# Amplifier_Module_C.net
KiCad netlist of a schematic drawn in EasyEDA Pro
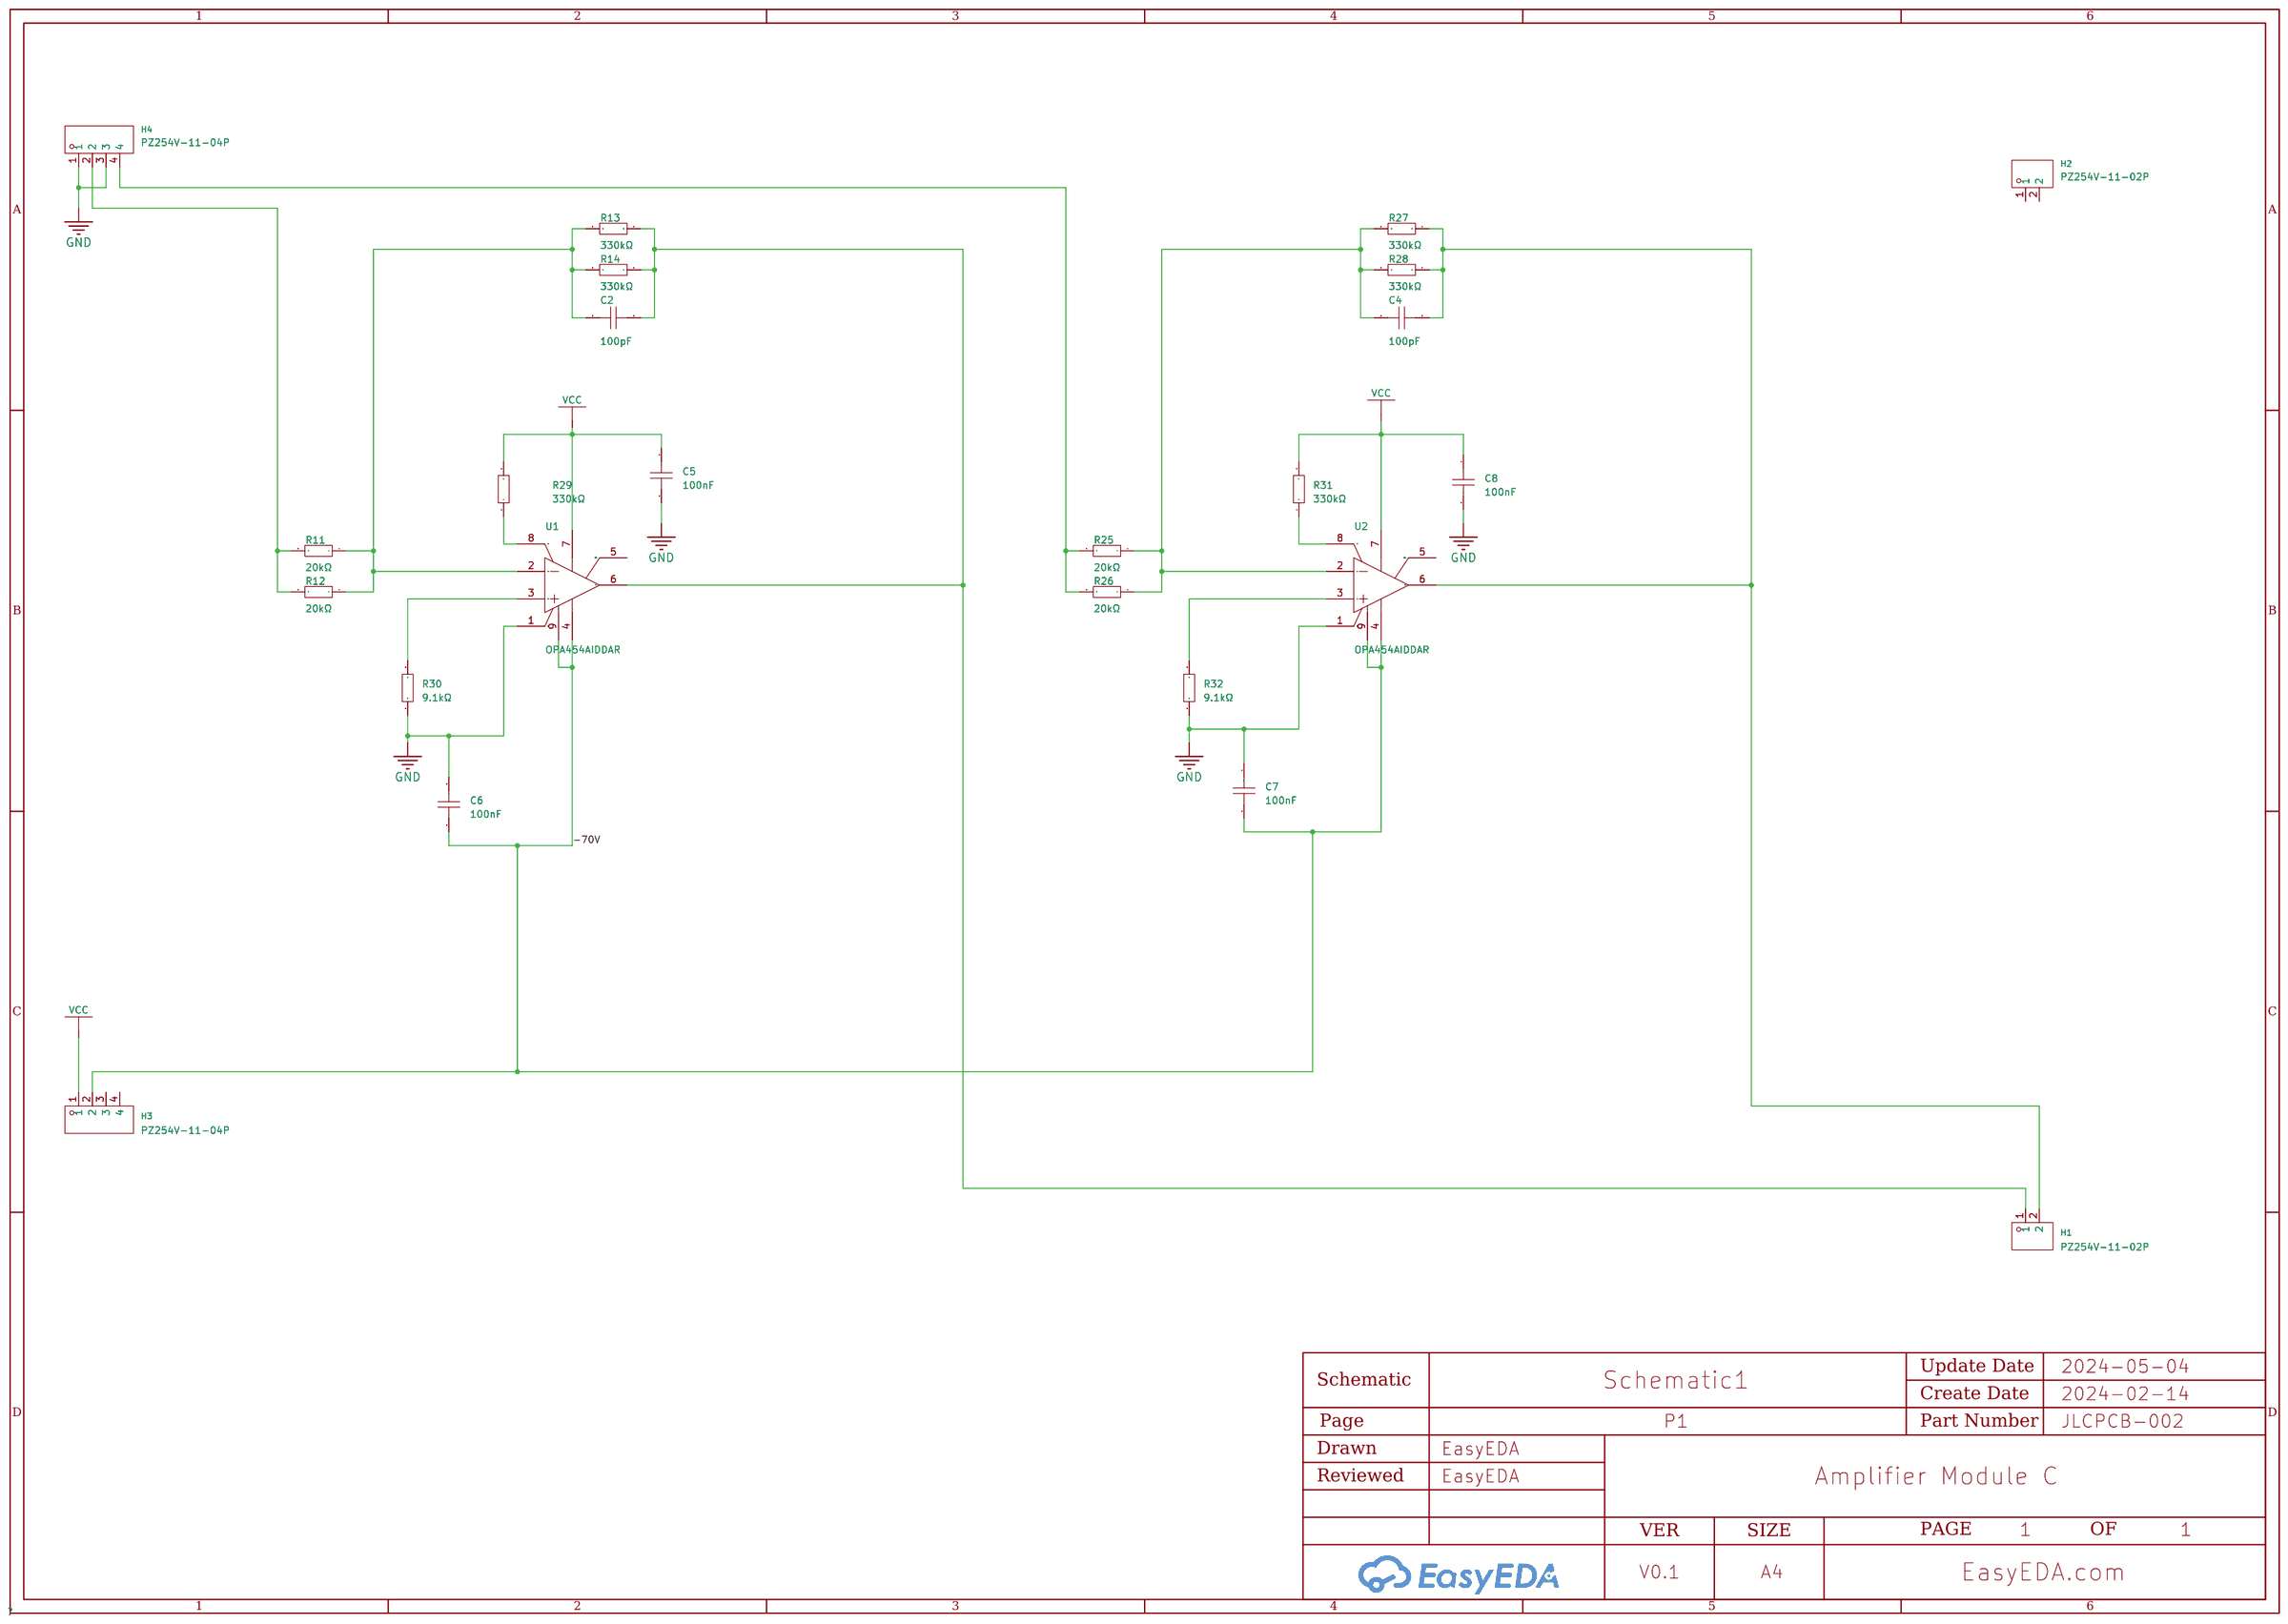
[diagram p0: schematic sheet]

(export (version "E")
  (design (tool "Eeschema 10.0.6"))
  (components
    (comp (ref "C2")
      (value "100pF")
      (footprint "easyedapro:C0603")
      (fields (field (name "Manufacturer Part") "0603CG101J101NT") (field (name "Manufacturer") "FH(风华)"))
      (libsource (lib "easyedapro") (part "CAP"))
    )
    (comp (ref "C4")
      (value "100pF")
      (footprint "easyedapro:C0603")
      (fields (field (name "Manufacturer Part") "0603CG101J101NT") (field (name "Manufacturer") "FH(风华)"))
      (libsource (lib "easyedapro") (part "CAP"))
    )
    (comp (ref "C5")
      (value "100nF")
      (footprint "easyedapro:C0603")
      (fields (field (name "Manufacturer Part") "0603B104K101NT") (field (name "Manufacturer") "FH(风华)"))
      (libsource (lib "easyedapro") (part "CAP"))
    )
    (comp (ref "C6")
      (value "100nF")
      (footprint "easyedapro:C0603")
      (fields (field (name "Manufacturer Part") "0603B104K101NT") (field (name "Manufacturer") "FH(风华)"))
      (libsource (lib "easyedapro") (part "CAP"))
    )
    (comp (ref "C7")
      (value "100nF")
      (footprint "easyedapro:C0603")
      (fields (field (name "Manufacturer Part") "0603B104K101NT") (field (name "Manufacturer") "FH(风华)"))
      (libsource (lib "easyedapro") (part "CAP"))
    )
    (comp (ref "C8")
      (value "100nF")
      (footprint "easyedapro:C0603")
      (fields (field (name "Manufacturer Part") "0603B104K101NT") (field (name "Manufacturer") "FH(风华)"))
      (libsource (lib "easyedapro") (part "CAP"))
    )
    (comp (ref "H1")
      (value "PZ254V-11-02P")
      (footprint "easyedapro:HDR-TH_2P-P2.54-V-M")
      (fields (field (name "Manufacturer") "XFCN(兴飞)"))
      (libsource (lib "easyedapro") (part "PZ254V-11-02P"))
    )
    (comp (ref "H2")
      (value "PZ254V-11-02P")
      (footprint "easyedapro:HDR-TH_2P-P2.54-V-M")
      (fields (field (name "Manufacturer") "XFCN(兴飞)"))
      (libsource (lib "easyedapro") (part "PZ254V-11-02P"))
    )
    (comp (ref "H3")
      (value "PZ254V-11-04P")
      (footprint "easyedapro:HDR-TH_4P-P2.54-V-M")
      (fields (field (name "Manufacturer") "XFCN(兴飞)"))
      (libsource (lib "easyedapro") (part "PZ254V-11-04P_C2691448"))
    )
    (comp (ref "H4")
      (value "PZ254V-11-04P")
      (footprint "easyedapro:HDR-TH_4P-P2.54-V-M")
      (fields (field (name "Manufacturer") "XFCN(兴飞)"))
      (libsource (lib "easyedapro") (part "PZ254V-11-04P_C2691448"))
    )
    (comp (ref "R11")
      (value "20kΩ")
      (footprint "easyedapro:R0603")
      (fields
        (field (name "Manufacturer Part") "0603WAF2002T5E")
        (field (name "Manufacturer") "UNI-ROYAL(厚声)")
      )
      (libsource (lib "easyedapro") (part "Res"))
    )
    (comp (ref "R12")
      (value "20kΩ")
      (footprint "easyedapro:R0603")
      (fields
        (field (name "Manufacturer Part") "0603WAF2002T5E")
        (field (name "Manufacturer") "UNI-ROYAL(厚声)")
      )
      (libsource (lib "easyedapro") (part "Res"))
    )
    (comp (ref "R13")
      (value "330kΩ")
      (footprint "easyedapro:R0603")
      (fields
        (field (name "Manufacturer Part") "0603WAF3303T5E")
        (field (name "Manufacturer") "UNI-ROYAL(厚声)")
      )
      (libsource (lib "easyedapro") (part "Res"))
    )
    (comp (ref "R14")
      (value "330kΩ")
      (footprint "easyedapro:R0603")
      (fields
        (field (name "Manufacturer Part") "0603WAF3303T5E")
        (field (name "Manufacturer") "UNI-ROYAL(厚声)")
      )
      (libsource (lib "easyedapro") (part "Res"))
    )
    (comp (ref "R25")
      (value "20kΩ")
      (footprint "easyedapro:R0603")
      (fields
        (field (name "Manufacturer Part") "0603WAF2002T5E")
        (field (name "Manufacturer") "UNI-ROYAL(厚声)")
      )
      (libsource (lib "easyedapro") (part "Res"))
    )
    (comp (ref "R26")
      (value "20kΩ")
      (footprint "easyedapro:R0603")
      (fields
        (field (name "Manufacturer Part") "0603WAF2002T5E")
        (field (name "Manufacturer") "UNI-ROYAL(厚声)")
      )
      (libsource (lib "easyedapro") (part "Res"))
    )
    (comp (ref "R27")
      (value "330kΩ")
      (footprint "easyedapro:R0603")
      (fields
        (field (name "Manufacturer Part") "0603WAF3303T5E")
        (field (name "Manufacturer") "UNI-ROYAL(厚声)")
      )
      (libsource (lib "easyedapro") (part "Res"))
    )
    (comp (ref "R28")
      (value "330kΩ")
      (footprint "easyedapro:R0603")
      (fields
        (field (name "Manufacturer Part") "0603WAF3303T5E")
        (field (name "Manufacturer") "UNI-ROYAL(厚声)")
      )
      (libsource (lib "easyedapro") (part "Res"))
    )
    (comp (ref "R29")
      (value "330kΩ")
      (footprint "easyedapro:R0603")
      (fields
        (field (name "Manufacturer Part") "0603WAF3303T5E")
        (field (name "Manufacturer") "UNI-ROYAL(厚声)")
      )
      (libsource (lib "easyedapro") (part "Res"))
    )
    (comp (ref "R30")
      (value "9.1kΩ")
      (footprint "easyedapro:R0603")
      (fields
        (field (name "Manufacturer Part") "0603WAF9101T5E")
        (field (name "Manufacturer") "UNI-ROYAL(厚声)")
      )
      (libsource (lib "easyedapro") (part "Res"))
    )
    (comp (ref "R31")
      (value "330kΩ")
      (footprint "easyedapro:R0603")
      (fields
        (field (name "Manufacturer Part") "0603WAF3303T5E")
        (field (name "Manufacturer") "UNI-ROYAL(厚声)")
      )
      (libsource (lib "easyedapro") (part "Res"))
    )
    (comp (ref "R32")
      (value "9.1kΩ")
      (footprint "easyedapro:R0603")
      (fields
        (field (name "Manufacturer Part") "0603WAF9101T5E")
        (field (name "Manufacturer") "UNI-ROYAL(厚声)")
      )
      (libsource (lib "easyedapro") (part "Res"))
    )
    (comp (ref "U1")
      (value "OPA454AIDDAR")
      (footprint "easyedapro:SOIC-8_L4.9-W3.9-P1.27-LS6.0-BL-EP")
      (fields (field (name "Manufacturer") "TI(德州仪器)"))
      (libsource (lib "easyedapro") (part "OPA454AIDDAR"))
    )
    (comp (ref "U2")
      (value "OPA454AIDDAR")
      (footprint "easyedapro:SOIC-8_L4.9-W3.9-P1.27-LS6.0-BL-EP")
      (fields (field (name "Manufacturer") "TI(德州仪器)"))
      (libsource (lib "easyedapro") (part "OPA454AIDDAR"))
    )
  )
  (nets
    (net (code "1") (name "/-70V") (class "Default")
      (node (ref "C6") (pin "2") (pinfunction "2_2") (pintype "input"))
      (node (ref "C7") (pin "2") (pinfunction "2_2") (pintype "input"))
      (node (ref "H3") (pin "2") (pinfunction "2_2") (pintype "input"))
      (node (ref "U1") (pin "4") (pinfunction "V-_4") (pintype "unspecified"))
      (node (ref "U1") (pin "9") (pinfunction "EP_9") (pintype "unspecified"))
      (node (ref "U2") (pin "4") (pinfunction "V-_4") (pintype "unspecified"))
      (node (ref "U2") (pin "9") (pinfunction "EP_9") (pintype "unspecified"))
    )
    (net (code "2") (name "GND") (class "Default")
      (node (ref "C5") (pin "2") (pinfunction "2_2") (pintype "input"))
      (node (ref "C6") (pin "1") (pinfunction "1_1") (pintype "input"))
      (node (ref "C7") (pin "1") (pinfunction "1_1") (pintype "input"))
      (node (ref "C8") (pin "2") (pinfunction "2_2") (pintype "input"))
      (node (ref "H4") (pin "1") (pinfunction "1_1") (pintype "input"))
      (node (ref "H4") (pin "3") (pinfunction "3_3") (pintype "input"))
      (node (ref "R30") (pin "1") (pinfunction "1_1") (pintype "input"))
      (node (ref "R32") (pin "1") (pinfunction "1_1") (pintype "input"))
      (node (ref "U1") (pin "1") (pinfunction "ED_COM_1") (pintype "unspecified"))
      (node (ref "U2") (pin "1") (pinfunction "ED_COM_1") (pintype "unspecified"))
    )
    (net (code "3") (name "Net-(H4-Pad2)") (class "Default")
      (node (ref "H4") (pin "2") (pinfunction "2_2") (pintype "input"))
      (node (ref "R11") (pin "2") (pinfunction "2_2") (pintype "input"))
      (node (ref "R12") (pin "2") (pinfunction "2_2") (pintype "input"))
    )
    (net (code "4") (name "Net-(H4-Pad4)") (class "Default")
      (node (ref "H4") (pin "4") (pinfunction "4_4") (pintype "input"))
      (node (ref "R25") (pin "2") (pinfunction "2_2") (pintype "input"))
      (node (ref "R26") (pin "2") (pinfunction "2_2") (pintype "input"))
    )
    (net (code "5") (name "Net-(U1-ED)") (class "Default")
      (node (ref "R29") (pin "1") (pinfunction "1_1") (pintype "input"))
      (node (ref "U1") (pin "8") (pinfunction "ED_8") (pintype "unspecified"))
    )
    (net (code "6") (name "Net-(U1-IN+)") (class "Default")
      (node (ref "R30") (pin "2") (pinfunction "2_2") (pintype "input"))
      (node (ref "U1") (pin "3") (pinfunction "IN+_3") (pintype "unspecified"))
    )
    (net (code "7") (name "Net-(U1-IN-)") (class "Default")
      (node (ref "C2") (pin "2") (pinfunction "2_2") (pintype "input"))
      (node (ref "R11") (pin "1") (pinfunction "1_1") (pintype "input"))
      (node (ref "R12") (pin "1") (pinfunction "1_1") (pintype "input"))
      (node (ref "R13") (pin "2") (pinfunction "2_2") (pintype "input"))
      (node (ref "R14") (pin "2") (pinfunction "2_2") (pintype "input"))
      (node (ref "U1") (pin "2") (pinfunction "IN-_2") (pintype "unspecified"))
    )
    (net (code "8") (name "Net-(U1-OUT)") (class "Default")
      (node (ref "C2") (pin "1") (pinfunction "1_1") (pintype "input"))
      (node (ref "H1") (pin "1") (pinfunction "1_1") (pintype "input"))
      (node (ref "R13") (pin "1") (pinfunction "1_1") (pintype "input"))
      (node (ref "R14") (pin "1") (pinfunction "1_1") (pintype "input"))
      (node (ref "U1") (pin "6") (pinfunction "OUT_6") (pintype "output"))
    )
    (net (code "9") (name "Net-(U2-ED)") (class "Default")
      (node (ref "R31") (pin "1") (pinfunction "1_1") (pintype "input"))
      (node (ref "U2") (pin "8") (pinfunction "ED_8") (pintype "unspecified"))
    )
    (net (code "10") (name "Net-(U2-IN+)") (class "Default")
      (node (ref "R32") (pin "2") (pinfunction "2_2") (pintype "input"))
      (node (ref "U2") (pin "3") (pinfunction "IN+_3") (pintype "unspecified"))
    )
    (net (code "11") (name "Net-(U2-IN-)") (class "Default")
      (node (ref "C4") (pin "2") (pinfunction "2_2") (pintype "input"))
      (node (ref "R25") (pin "1") (pinfunction "1_1") (pintype "input"))
      (node (ref "R26") (pin "1") (pinfunction "1_1") (pintype "input"))
      (node (ref "R27") (pin "2") (pinfunction "2_2") (pintype "input"))
      (node (ref "R28") (pin "2") (pinfunction "2_2") (pintype "input"))
      (node (ref "U2") (pin "2") (pinfunction "IN-_2") (pintype "unspecified"))
    )
    (net (code "12") (name "Net-(U2-OUT)") (class "Default")
      (node (ref "C4") (pin "1") (pinfunction "1_1") (pintype "input"))
      (node (ref "H1") (pin "2") (pinfunction "2_2") (pintype "input"))
      (node (ref "R27") (pin "1") (pinfunction "1_1") (pintype "input"))
      (node (ref "R28") (pin "1") (pinfunction "1_1") (pintype "input"))
      (node (ref "U2") (pin "6") (pinfunction "OUT_6") (pintype "output"))
    )
    (net (code "13") (name "VCC") (class "Default")
      (node (ref "C5") (pin "1") (pinfunction "1_1") (pintype "input"))
      (node (ref "C8") (pin "1") (pinfunction "1_1") (pintype "input"))
      (node (ref "H3") (pin "1") (pinfunction "1_1") (pintype "input"))
      (node (ref "R29") (pin "2") (pinfunction "2_2") (pintype "input"))
      (node (ref "R31") (pin "2") (pinfunction "2_2") (pintype "input"))
      (node (ref "U1") (pin "7") (pinfunction "V+_7") (pintype "unspecified"))
      (node (ref "U2") (pin "7") (pinfunction "V+_7") (pintype "unspecified"))
    )
    (net (code "14") (name "unconnected-(H2-Pad1)") (class "Default")
      (node (ref "H2") (pin "1") (pinfunction "1_1") (pintype "input"))
    )
    (net (code "15") (name "unconnected-(H2-Pad2)") (class "Default")
      (node (ref "H2") (pin "2") (pinfunction "2_2") (pintype "input"))
    )
    (net (code "16") (name "unconnected-(H3-Pad3)") (class "Default")
      (node (ref "H3") (pin "3") (pinfunction "3_3") (pintype "input"))
    )
    (net (code "17") (name "unconnected-(H3-Pad4)") (class "Default")
      (node (ref "H3") (pin "4") (pinfunction "4_4") (pintype "input"))
    )
    (net (code "18") (name "unconnected-(U1-STATUS_FLAG-Pad5)") (class "Default")
      (node (ref "U1") (pin "5") (pinfunction "STATUS_FLAG_5") (pintype "unspecified"))
    )
    (net (code "19") (name "unconnected-(U2-STATUS_FLAG-Pad5)") (class "Default")
      (node (ref "U2") (pin "5") (pinfunction "STATUS_FLAG_5") (pintype "unspecified"))
    )
  )
)
